# MirZ21_Sub-D.net
KiCad netlist of a schematic drawn in EAGLE
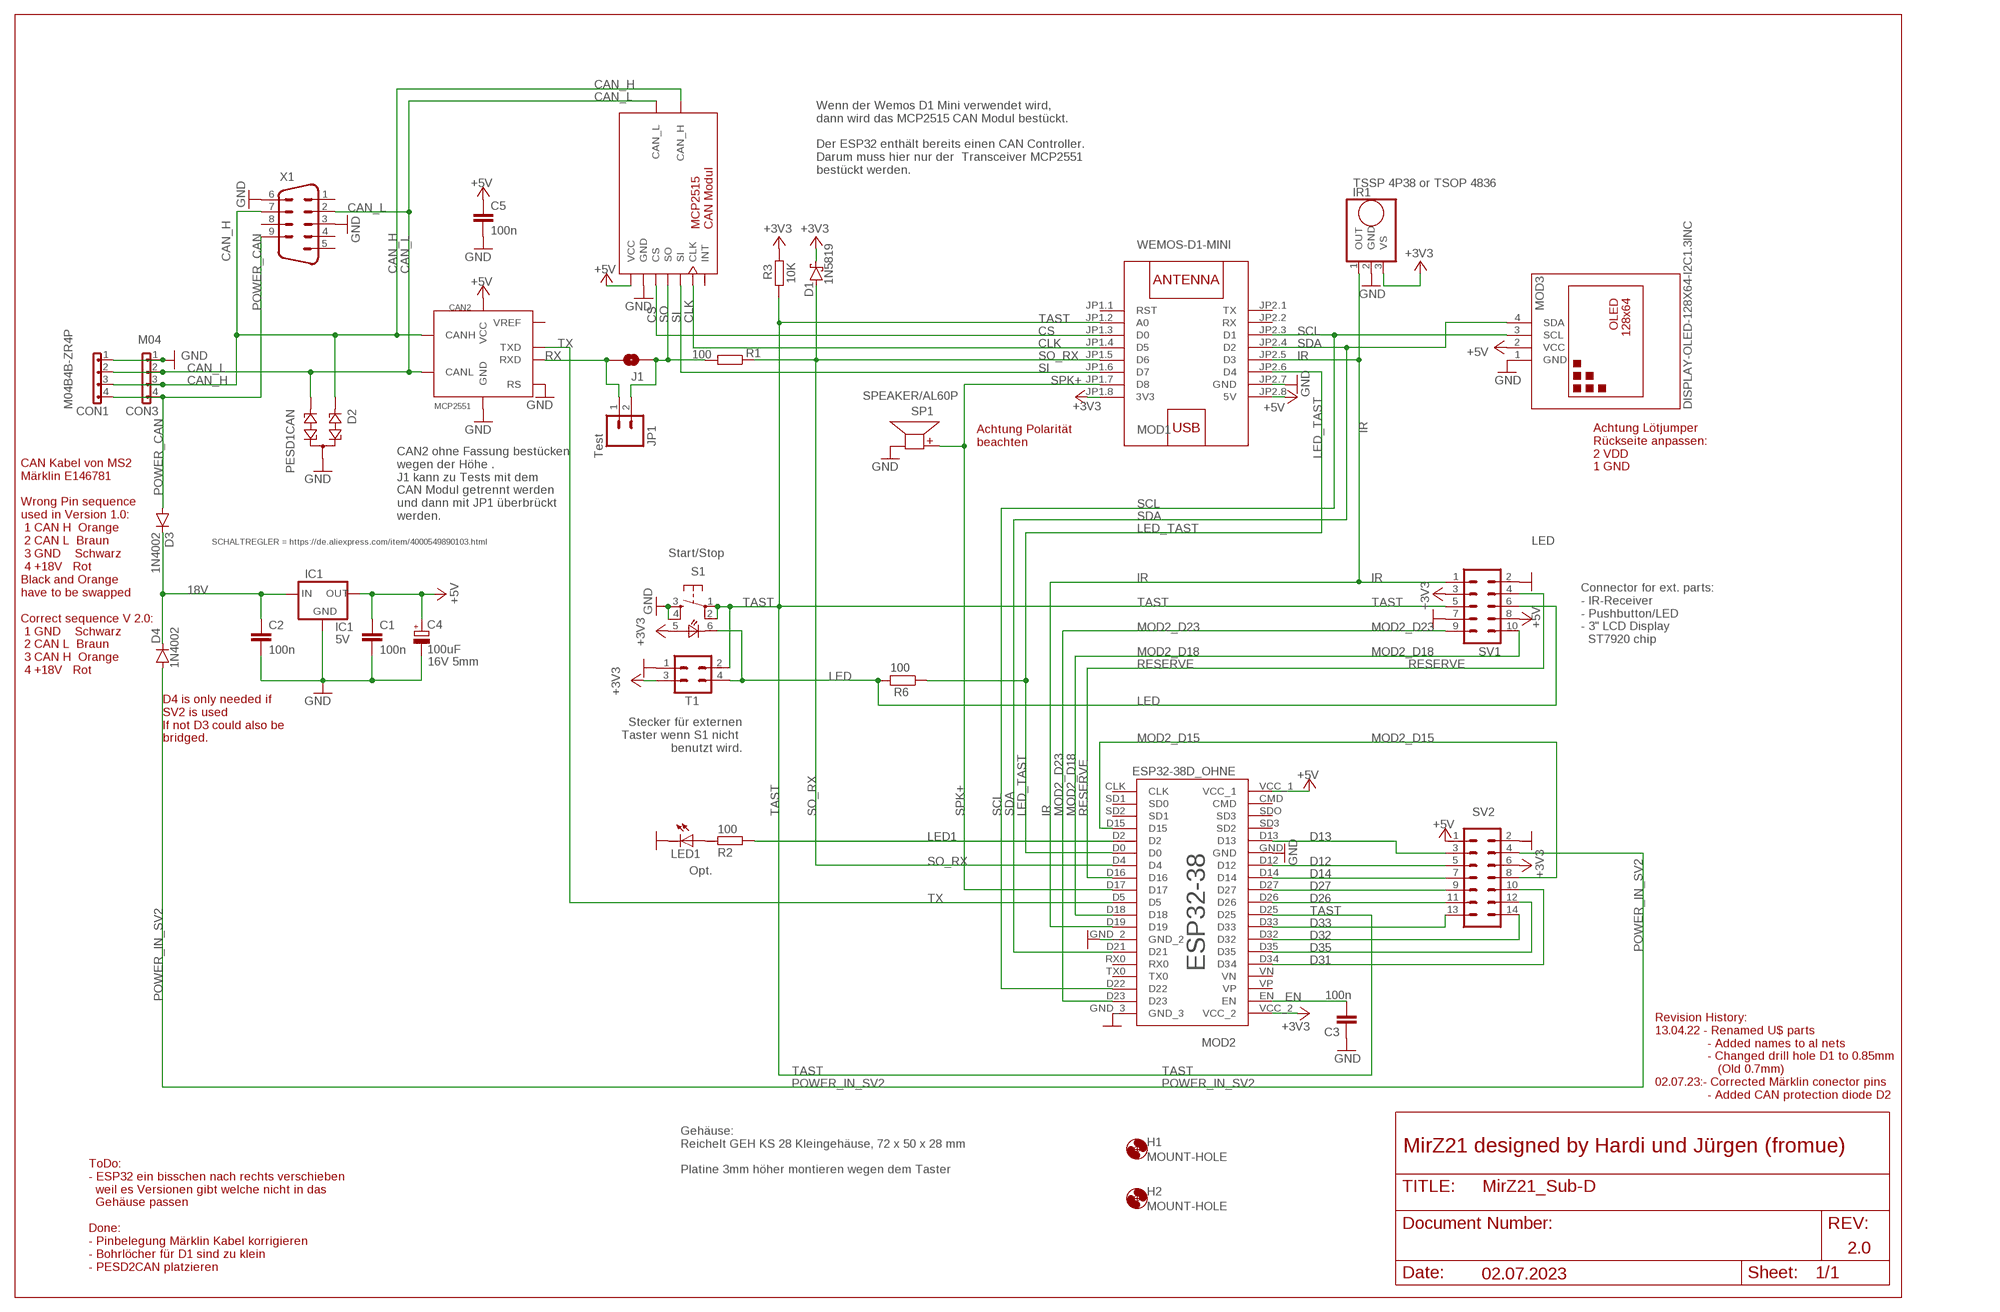
[diagram p0: schematic, sheet 1]

(export (version "E")
  (design (tool "Eeschema 10.0.6"))
  (components
    (comp (ref "C1")
      (value "100n")
      (footprint "eagle-import:C025-025X050")
      (libsource (lib "eagle-import") (part "C-EU025-025X050"))
    )
    (comp (ref "C2")
      (value "100n")
      (footprint "eagle-import:C025-025X050")
      (libsource (lib "eagle-import") (part "C-EU025-025X050"))
    )
    (comp (ref "C3")
      (value "100n")
      (footprint "eagle-import:C025-025X050")
      (libsource (lib "eagle-import") (part "C-EU025-025X050"))
    )
    (comp (ref "C4")
      (value "100uF")
      (footprint "eagle-import:TT2D5L")
      (fields (field (name "ADD") "16V 5mm"))
      (libsource (lib "eagle-import") (part "CPOL-EUTT2D5L"))
    )
    (comp (ref "C5")
      (value "100n")
      (footprint "eagle-import:C025-025X050")
      (libsource (lib "eagle-import") (part "C-EU025-025X050"))
    )
    (comp (ref "CAN1")
      (value "MCP2515_CAN_CUTCUT")
      (footprint "eagle-import:MCP2515_CAN_CUT")
      (libsource (lib "eagle-import") (part "MCP2515_CAN_CUTCUT"))
    )
    (comp (ref "CAN2")
      (value "MCP2551")
      (footprint "eagle-import:DIP08")
      (libsource (lib "eagle-import") (part "MCP2551DIP"))
    )
    (comp (ref "CON1")
      (value "M04B4B-ZR4P")
      (footprint "eagle-import:B4B-ZR4P")
      (libsource (lib "eagle-import") (part "M04B4B-ZR4P"))
    )
    (comp (ref "CON3")
      (value "M04")
      (footprint "eagle-import:1X04")
      (libsource (lib "eagle-import") (part "M04"))
    )
    (comp (ref "D1")
      (value "1N5819")
      (footprint "eagle-import:DO41-7.6")
      (libsource (lib "eagle-import") (part "1N581"))
    )
    (comp (ref "D2")
      (value "PESD1CAN")
      (footprint "eagle-import:SOT23")
      (libsource (lib "eagle-import") (part "PESD1CAN"))
    )
    (comp (ref "D3")
      (value "1N4002")
      (footprint "eagle-import:DO41-10")
      (libsource (lib "eagle-import") (part "1N4004"))
    )
    (comp (ref "D4")
      (value "1N4002")
      (footprint "eagle-import:DO41-10")
      (libsource (lib "eagle-import") (part "1N4004"))
    )
    (comp (ref "H1")
      (value "MOUNT-HOLE")
      (footprint "eagle-import:GEH_KS")
      (libsource (lib "eagle-import") (part "MOUNT-HOLE"))
    )
    (comp (ref "H2")
      (value "MOUNT-HOLE")
      (footprint "eagle-import:GEH_KS")
      (libsource (lib "eagle-import") (part "MOUNT-HOLE"))
    )
    (comp (ref "IC1")
      (value "5V")
      (footprint "eagle-import:HX1314G")
      (fields (field (name "SCHALTREGLER") "https://de.aliexpress.com/item/4000549890103.html"))
      (libsource (lib "eagle-import") (part "78XXSSTEPDOWN"))
    )
    (comp (ref "IR1")
      (value "TSSP 4P38 or TSOP 4836")
      (footprint "eagle-import:TSSP4P38")
      (libsource (lib "eagle-import") (part "TSSP4P38"))
    )
    (comp (ref "J1")
      (value "SOLDERJUMPERTRACE")
      (footprint "eagle-import:SJ_2S-TRACE")
      (libsource (lib "eagle-import") (part "SOLDERJUMPERTRACE"))
    )
    (comp (ref "JP1")
      (value "Test")
      (footprint "eagle-import:1X02")
      (libsource (lib "eagle-import") (part "M02PTH"))
    )
    (comp (ref "LED1")
      (value "Opt.")
      (footprint "eagle-import:LED3MM")
      (libsource (lib "eagle-import") (part "LED3MM"))
    )
    (comp (ref "MOD1")
      (value "WEMOS-D1-MINI")
      (footprint "eagle-import:WEMOS-D1-MINI")
      (libsource (lib "eagle-import") (part "WEMOS-D1-MINI"))
    )
    (comp (ref "MOD2")
      (value "ESP32-38D_OHNE")
      (footprint "eagle-import:ESP32-38D_0")
      (libsource (lib "eagle-import") (part "ESP32-38D_OHNE"))
    )
    (comp (ref "MOD3")
      (value "DISPLAY-OLED-128X64-I2C1.3INC")
      (footprint "eagle-import:DISPLAY-OLED-128X64-I2C-1.3")
      (libsource (lib "eagle-import") (part "DISPLAY-OLED-128X64-I2C1.3INC"))
    )
    (comp (ref "R1")
      (value "100")
      (footprint "eagle-import:0204_7")
      (libsource (lib "eagle-import") (part "R0204/7"))
    )
    (comp (ref "R2")
      (value "100")
      (footprint "eagle-import:0207_2V")
      (libsource (lib "eagle-import") (part "R-EU_0207/2V"))
    )
    (comp (ref "R3")
      (value "10K")
      (footprint "eagle-import:0204_7")
      (libsource (lib "eagle-import") (part "R0204/7"))
    )
    (comp (ref "R6")
      (value "100")
      (footprint "eagle-import:0204_7")
      (libsource (lib "eagle-import") (part "R0204/7"))
    )
    (comp (ref "S1")
      (value "TASTER_LEDTC-1198-B")
      (footprint "eagle-import:TASTER_LED")
      (libsource (lib "eagle-import") (part "TASTER_LEDTC-1198-B"))
    )
    (comp (ref "SP1")
      (value "SPEAKER/AL60P")
      (footprint "eagle-import:RMP-14SP")
      (libsource (lib "eagle-import") (part "SPEAKER/AL60P"))
    )
    (comp (ref "SV1")
      (value "ML10")
      (footprint "eagle-import:ML10")
      (libsource (lib "eagle-import") (part "ML10"))
    )
    (comp (ref "SV2")
      (value "ML14")
      (footprint "eagle-import:ML14")
      (libsource (lib "eagle-import") (part "ML14"))
    )
    (comp (ref "T1")
      (value "CON-HARTING-ML_ML4ML4_FEMALE")
      (footprint "eagle-import:ML_ML4_FEMALE")
      (libsource (lib "eagle-import") (part "CON-HARTING-ML_ML4ML4_FEMALE"))
    )
    (comp (ref "X1")
      (value "M09D")
      (footprint "eagle-import:M09D")
      (libsource (lib "eagle-import") (part "M09D"))
    )
  )
  (nets
    (net (code "1") (name "+3V3") (class "Default")
      (node (ref "D1") (pin "C") (pinfunction "C_C") (pintype "passive"))
      (node (ref "IR1") (pin "3") (pinfunction "VS_3") (pintype "power_in"))
      (node (ref "MOD1") (pin "JP1.8") (pinfunction "3V3_JP1.8") (pintype "power_in"))
      (node (ref "MOD2") (pin "VCC_2") (pinfunction "VCC_2_VCC_2") (pintype "power_in"))
      (node (ref "R3") (pin "2") (pinfunction "2_2") (pintype "passive"))
      (node (ref "S1") (pin "5") (pinfunction "+_5") (pintype "input"))
      (node (ref "SV1") (pin "3") (pinfunction "3_3") (pintype "passive"))
      (node (ref "SV2") (pin "6") (pinfunction "6_6") (pintype "passive"))
      (node (ref "T1") (pin "3") (pinfunction "3_3") (pintype "passive"))
    )
    (net (code "2") (name "+5V") (class "Default")
      (node (ref "C1") (pin "1") (pinfunction "1_1") (pintype "passive"))
      (node (ref "C4") (pin "+") (pinfunction "+_+") (pintype "passive"))
      (node (ref "C5") (pin "1") (pinfunction "1_1") (pintype "passive"))
      (node (ref "CAN1") (pin "1") (pinfunction "VCC_1") (pintype "power_in"))
      (node (ref "CAN2") (pin "3") (pinfunction "VCC_3") (pintype "power_in"))
      (node (ref "IC1") (pin "OUT") (pinfunction "OUT_OUT") (pintype "passive"))
      (node (ref "MOD1") (pin "JP2.8") (pinfunction "5V_JP2.8") (pintype "power_in"))
      (node (ref "MOD2") (pin "VCC_1") (pinfunction "VCC_1_VCC_1") (pintype "power_in"))
      (node (ref "MOD3") (pin "2") (pinfunction "VCC_2") (pintype "power_in"))
      (node (ref "SV1") (pin "8") (pinfunction "8_8") (pintype "passive"))
      (node (ref "SV2") (pin "1") (pinfunction "1_1") (pintype "passive"))
    )
    (net (code "3") (name "/18V") (class "Default")
      (node (ref "C2") (pin "1") (pinfunction "1_1") (pintype "passive"))
      (node (ref "D3") (pin "C") (pinfunction "C_C") (pintype "passive"))
      (node (ref "D4") (pin "C") (pinfunction "C_C") (pintype "passive"))
      (node (ref "IC1") (pin "IN") (pinfunction "IN_IN") (pintype "input"))
    )
    (net (code "4") (name "/CAN_H") (class "Default")
      (node (ref "CAN1") (pin "9") (pinfunction "CAN_H_9") (pintype "bidirectional"))
      (node (ref "CAN2") (pin "7") (pinfunction "CANH_7") (pintype "bidirectional"))
      (node (ref "CON1") (pin "3") (pinfunction "3_3") (pintype "passive"))
      (node (ref "CON3") (pin "3") (pinfunction "3_3") (pintype "passive"))
      (node (ref "D2") (pin "1") (pinfunction "1_1") (pintype "passive"))
      (node (ref "X1") (pin "7") (pinfunction "7_7") (pintype "passive"))
    )
    (net (code "5") (name "/CAN_L") (class "Default")
      (node (ref "CAN1") (pin "8") (pinfunction "CAN_L_8") (pintype "bidirectional"))
      (node (ref "CAN2") (pin "6") (pinfunction "CANL_6") (pintype "bidirectional"))
      (node (ref "CON1") (pin "2") (pinfunction "2_2") (pintype "passive"))
      (node (ref "CON3") (pin "2") (pinfunction "2_2") (pintype "passive"))
      (node (ref "D2") (pin "2") (pinfunction "2_2") (pintype "passive"))
      (node (ref "X1") (pin "2") (pinfunction "2_2") (pintype "passive"))
    )
    (net (code "6") (name "/CLK") (class "Default")
      (node (ref "CAN1") (pin "6") (pinfunction "CLK_6") (pintype "input"))
      (node (ref "MOD1") (pin "JP1.4") (pinfunction "D5_JP1.4") (pintype "bidirectional"))
    )
    (net (code "7") (name "/CS") (class "Default")
      (node (ref "CAN1") (pin "3") (pinfunction "CS_3") (pintype "input"))
      (node (ref "MOD1") (pin "JP1.3") (pinfunction "D0_JP1.3") (pintype "bidirectional"))
    )
    (net (code "8") (name "/D12") (class "Default")
      (node (ref "MOD2") (pin "D12") (pinfunction "D12_D12") (pintype "bidirectional"))
      (node (ref "SV2") (pin "5") (pinfunction "5_5") (pintype "passive"))
    )
    (net (code "9") (name "/D13") (class "Default")
      (node (ref "MOD2") (pin "D13") (pinfunction "D13_D13") (pintype "bidirectional"))
      (node (ref "SV2") (pin "3") (pinfunction "3_3") (pintype "passive"))
    )
    (net (code "10") (name "/D14") (class "Default")
      (node (ref "MOD2") (pin "D14") (pinfunction "D14_D14") (pintype "bidirectional"))
      (node (ref "SV2") (pin "7") (pinfunction "7_7") (pintype "passive"))
    )
    (net (code "11") (name "/D26") (class "Default")
      (node (ref "MOD2") (pin "D26") (pinfunction "D26_D26") (pintype "bidirectional"))
      (node (ref "SV2") (pin "11") (pinfunction "11_11") (pintype "passive"))
    )
    (net (code "12") (name "/D27") (class "Default")
      (node (ref "MOD2") (pin "D27") (pinfunction "D27_D27") (pintype "bidirectional"))
      (node (ref "SV2") (pin "9") (pinfunction "9_9") (pintype "passive"))
    )
    (net (code "13") (name "/D31") (class "Default")
      (node (ref "MOD2") (pin "D34") (pinfunction "D34_D34") (pintype "bidirectional"))
      (node (ref "SV2") (pin "10") (pinfunction "10_10") (pintype "passive"))
    )
    (net (code "14") (name "/D32") (class "Default")
      (node (ref "MOD2") (pin "D32") (pinfunction "D32_D32") (pintype "bidirectional"))
      (node (ref "SV2") (pin "14") (pinfunction "14_14") (pintype "passive"))
    )
    (net (code "15") (name "/D33") (class "Default")
      (node (ref "MOD2") (pin "D33") (pinfunction "D33_D33") (pintype "bidirectional"))
      (node (ref "SV2") (pin "13") (pinfunction "13_13") (pintype "passive"))
    )
    (net (code "16") (name "/D35") (class "Default")
      (node (ref "MOD2") (pin "D35") (pinfunction "D35_D35") (pintype "bidirectional"))
      (node (ref "SV2") (pin "12") (pinfunction "12_12") (pintype "passive"))
    )
    (net (code "17") (name "/EN") (class "Default")
      (node (ref "C3") (pin "2") (pinfunction "2_2") (pintype "passive"))
      (node (ref "MOD2") (pin "EN") (pinfunction "EN_EN") (pintype "input"))
    )
    (net (code "18") (name "/IR") (class "Default")
      (node (ref "IR1") (pin "1") (pinfunction "OUT_1") (pintype "output"))
      (node (ref "MOD1") (pin "JP2.5") (pinfunction "D3_JP2.5") (pintype "bidirectional"))
      (node (ref "MOD2") (pin "D19") (pinfunction "D19_D19") (pintype "bidirectional"))
      (node (ref "SV1") (pin "1") (pinfunction "1_1") (pintype "passive"))
    )
    (net (code "19") (name "/LED") (class "Default")
      (node (ref "R6") (pin "2") (pinfunction "2_2") (pintype "passive"))
      (node (ref "S1") (pin "6") (pinfunction "-_6") (pintype "input"))
      (node (ref "SV1") (pin "6") (pinfunction "6_6") (pintype "passive"))
      (node (ref "T1") (pin "4") (pinfunction "4_4") (pintype "passive"))
    )
    (net (code "20") (name "/LED1") (class "Default")
      (node (ref "MOD2") (pin "D2") (pinfunction "D2_D2") (pintype "bidirectional"))
      (node (ref "R2") (pin "2") (pinfunction "2_2") (pintype "passive"))
    )
    (net (code "21") (name "/LED_TAST") (class "Default")
      (node (ref "MOD1") (pin "JP2.6") (pinfunction "D4_JP2.6") (pintype "bidirectional"))
      (node (ref "MOD2") (pin "D0") (pinfunction "D0_D0") (pintype "input"))
      (node (ref "R6") (pin "1") (pinfunction "1_1") (pintype "passive"))
    )
    (net (code "22") (name "/MOD2_D15") (class "Default")
      (node (ref "MOD2") (pin "D15") (pinfunction "D15_D15") (pintype "bidirectional"))
      (node (ref "SV2") (pin "8") (pinfunction "8_8") (pintype "passive"))
    )
    (net (code "23") (name "/MOD2_D18") (class "Default")
      (node (ref "MOD2") (pin "D18") (pinfunction "D18_D18") (pintype "bidirectional"))
      (node (ref "SV1") (pin "10") (pinfunction "10_10") (pintype "passive"))
    )
    (net (code "24") (name "/MOD2_D23") (class "Default")
      (node (ref "MOD2") (pin "D23") (pinfunction "D23_D23") (pintype "bidirectional"))
      (node (ref "SV1") (pin "9") (pinfunction "9_9") (pintype "passive"))
    )
    (net (code "25") (name "/POWER_CAN") (class "Default")
      (node (ref "CON1") (pin "4") (pinfunction "4_4") (pintype "passive"))
      (node (ref "CON3") (pin "4") (pinfunction "4_4") (pintype "passive"))
      (node (ref "D3") (pin "A") (pinfunction "A_A") (pintype "passive"))
      (node (ref "X1") (pin "9") (pinfunction "9_9") (pintype "passive"))
    )
    (net (code "26") (name "/POWER_IN_SV2") (class "Default")
      (node (ref "D4") (pin "A") (pinfunction "A_A") (pintype "passive"))
      (node (ref "SV2") (pin "4") (pinfunction "4_4") (pintype "passive"))
    )
    (net (code "27") (name "/RESERVE") (class "Default")
      (node (ref "MOD2") (pin "D16") (pinfunction "D16_D16") (pintype "bidirectional"))
      (node (ref "SV1") (pin "4") (pinfunction "4_4") (pintype "passive"))
    )
    (net (code "28") (name "/RX") (class "Default")
      (node (ref "CAN2") (pin "4") (pinfunction "RXD_4") (pintype "power_in"))
      (node (ref "J1") (pin "2") (pinfunction "2_2") (pintype "passive"))
      (node (ref "JP1") (pin "1") (pinfunction "1_1") (pintype "passive"))
    )
    (net (code "29") (name "/SCL") (class "Default")
      (node (ref "MOD1") (pin "JP2.3") (pinfunction "D1_JP2.3") (pintype "bidirectional"))
      (node (ref "MOD2") (pin "D22") (pinfunction "D22_D22") (pintype "bidirectional"))
      (node (ref "MOD3") (pin "3") (pinfunction "SCL_3") (pintype "bidirectional"))
    )
    (net (code "30") (name "/SDA") (class "Default")
      (node (ref "MOD1") (pin "JP2.4") (pinfunction "D2_JP2.4") (pintype "bidirectional"))
      (node (ref "MOD2") (pin "D21") (pinfunction "D21_D21") (pintype "bidirectional"))
      (node (ref "MOD3") (pin "4") (pinfunction "SDA_4") (pintype "bidirectional"))
    )
    (net (code "31") (name "/SI") (class "Default")
      (node (ref "CAN1") (pin "5") (pinfunction "SI_5") (pintype "input"))
      (node (ref "MOD1") (pin "JP1.6") (pinfunction "D7_JP1.6") (pintype "bidirectional"))
    )
    (net (code "32") (name "/SO") (class "Default")
      (node (ref "CAN1") (pin "4") (pinfunction "SO_4") (pintype "output"))
      (node (ref "J1") (pin "1") (pinfunction "1_1") (pintype "passive"))
      (node (ref "JP1") (pin "2") (pinfunction "2_2") (pintype "passive"))
      (node (ref "R1") (pin "2") (pinfunction "2_2") (pintype "passive"))
    )
    (net (code "33") (name "/SO_RX") (class "Default")
      (node (ref "D1") (pin "A") (pinfunction "A_A") (pintype "passive"))
      (node (ref "MOD1") (pin "JP1.5") (pinfunction "D6_JP1.5") (pintype "bidirectional"))
      (node (ref "MOD2") (pin "D4") (pinfunction "D4_D4") (pintype "bidirectional"))
      (node (ref "R1") (pin "1") (pinfunction "1_1") (pintype "passive"))
    )
    (net (code "34") (name "/SPK+") (class "Default")
      (node (ref "MOD1") (pin "JP1.7") (pinfunction "D8_JP1.7") (pintype "bidirectional"))
      (node (ref "MOD2") (pin "D17") (pinfunction "D17_D17") (pintype "bidirectional"))
      (node (ref "SP1") (pin "1") (pinfunction "+_1") (pintype "passive"))
    )
    (net (code "35") (name "/TAST") (class "Default")
      (node (ref "MOD1") (pin "JP1.2") (pinfunction "A0_JP1.2") (pintype "bidirectional"))
      (node (ref "MOD2") (pin "D25") (pinfunction "D25_D25") (pintype "bidirectional"))
      (node (ref "R3") (pin "1") (pinfunction "1_1") (pintype "passive"))
      (node (ref "S1") (pin "1") (pinfunction "P_1") (pintype "passive"))
      (node (ref "S1") (pin "2") (pinfunction "P1_2") (pintype "passive"))
      (node (ref "SV1") (pin "5") (pinfunction "5_5") (pintype "passive"))
      (node (ref "T1") (pin "2") (pinfunction "2_2") (pintype "passive"))
    )
    (net (code "36") (name "/TX") (class "Default")
      (node (ref "CAN2") (pin "1") (pinfunction "TXD_1") (pintype "power_in"))
      (node (ref "MOD2") (pin "D5") (pinfunction "D5_D5") (pintype "bidirectional"))
    )
    (net (code "37") (name "/VREF") (class "Default")
      (node (ref "CAN2") (pin "5") (pinfunction "VREF_5") (pintype "power_in"))
    )
    (net (code "38") (name "GND") (class "Default")
      (node (ref "C1") (pin "2") (pinfunction "2_2") (pintype "passive"))
      (node (ref "C2") (pin "2") (pinfunction "2_2") (pintype "passive"))
      (node (ref "C3") (pin "1") (pinfunction "1_1") (pintype "passive"))
      (node (ref "C4") (pin "-") (pinfunction "-_-") (pintype "passive"))
      (node (ref "C5") (pin "2") (pinfunction "2_2") (pintype "passive"))
      (node (ref "CAN1") (pin "2") (pinfunction "GND_2") (pintype "power_in"))
      (node (ref "CAN2") (pin "2") (pinfunction "GND_2") (pintype "power_in"))
      (node (ref "CAN2") (pin "8") (pinfunction "RS_8") (pintype "power_in"))
      (node (ref "CON1") (pin "1") (pinfunction "1_1") (pintype "passive"))
      (node (ref "CON3") (pin "1") (pinfunction "1_1") (pintype "passive"))
      (node (ref "D2") (pin "3") (pinfunction "3_3") (pintype "passive"))
      (node (ref "IC1") (pin "GND") (pinfunction "GND_GND") (pintype "input"))
      (node (ref "IR1") (pin "2") (pinfunction "GND_2") (pintype "power_in"))
      (node (ref "LED1") (pin "K") (pinfunction "C_K") (pintype "passive"))
      (node (ref "MOD1") (pin "JP2.7") (pinfunction "GND_JP2.7") (pintype "power_in"))
      (node (ref "MOD2") (pin "GND") (pinfunction "GND_GND") (pintype "power_in"))
      (node (ref "MOD2") (pin "GND_2") (pinfunction "GND_2_GND_2") (pintype "power_in"))
      (node (ref "MOD2") (pin "GND_3") (pinfunction "GND_3_GND_3") (pintype "power_in"))
      (node (ref "MOD3") (pin "1") (pinfunction "GND_1") (pintype "power_in"))
      (node (ref "S1") (pin "3") (pinfunction "S_3") (pintype "passive"))
      (node (ref "S1") (pin "4") (pinfunction "S1_4") (pintype "passive"))
      (node (ref "SP1") (pin "2") (pinfunction "-_2") (pintype "passive"))
      (node (ref "SV1") (pin "2") (pinfunction "2_2") (pintype "passive"))
      (node (ref "SV1") (pin "7") (pinfunction "7_7") (pintype "passive"))
      (node (ref "SV2") (pin "2") (pinfunction "2_2") (pintype "passive"))
      (node (ref "T1") (pin "1") (pinfunction "1_1") (pintype "passive"))
      (node (ref "X1") (pin "3") (pinfunction "3_3") (pintype "passive"))
      (node (ref "X1") (pin "6") (pinfunction "6_6") (pintype "passive"))
    )
    (net (code "39") (name "Net-(LED1-PadA)") (class "Default")
      (node (ref "LED1") (pin "A") (pinfunction "A_A") (pintype "passive"))
      (node (ref "R2") (pin "1") (pinfunction "1_1") (pintype "passive"))
    )
    (net (code "40") (name "unconnected-(CAN1-INT-Pad7)") (class "Default")
      (node (ref "CAN1") (pin "7") (pinfunction "INT_7") (pintype "open_collector"))
    )
    (net (code "41") (name "unconnected-(MOD1-RST-PadJP1.1)") (class "Default")
      (node (ref "MOD1") (pin "JP1.1") (pinfunction "RST_JP1.1") (pintype "bidirectional"))
    )
    (net (code "42") (name "unconnected-(MOD1-RX-PadJP2.2)") (class "Default")
      (node (ref "MOD1") (pin "JP2.2") (pinfunction "RX_JP2.2") (pintype "bidirectional"))
    )
    (net (code "43") (name "unconnected-(MOD1-TX-PadJP2.1)") (class "Default")
      (node (ref "MOD1") (pin "JP2.1") (pinfunction "TX_JP2.1") (pintype "bidirectional"))
    )
    (net (code "44") (name "unconnected-(MOD2-PadCLK)") (class "Default")
      (node (ref "MOD2") (pin "CLK") (pinfunction "CLK_CLK") (pintype "no_connect"))
    )
    (net (code "45") (name "unconnected-(MOD2-PadCMD)") (class "Default")
      (node (ref "MOD2") (pin "CMD") (pinfunction "CMD_CMD") (pintype "no_connect"))
    )
    (net (code "46") (name "unconnected-(MOD2-PadRX0)") (class "Default")
      (node (ref "MOD2") (pin "RX0") (pinfunction "RX0_RX0") (pintype "bidirectional"))
    )
    (net (code "47") (name "unconnected-(MOD2-PadTX0)") (class "Default")
      (node (ref "MOD2") (pin "TX0") (pinfunction "TX0_TX0") (pintype "bidirectional"))
    )
    (net (code "48") (name "unconnected-(MOD2-PadVN)") (class "Default")
      (node (ref "MOD2") (pin "VN") (pinfunction "VN_VN") (pintype "bidirectional"))
    )
    (net (code "49") (name "unconnected-(MOD2-PadVP)") (class "Default")
      (node (ref "MOD2") (pin "VP") (pinfunction "VP_VP") (pintype "bidirectional"))
    )
    (net (code "50") (name "unconnected-(MOD2-SD0-PadSD1)") (class "Default")
      (node (ref "MOD2") (pin "SD1") (pinfunction "SD0_SD1") (pintype "no_connect"))
    )
    (net (code "51") (name "unconnected-(MOD2-SD1-PadSD2)") (class "Default")
      (node (ref "MOD2") (pin "SD2") (pinfunction "SD1_SD2") (pintype "no_connect"))
    )
    (net (code "52") (name "unconnected-(MOD2-SD2-PadSD3)") (class "Default")
      (node (ref "MOD2") (pin "SD3") (pinfunction "SD2_SD3") (pintype "no_connect"))
    )
    (net (code "53") (name "unconnected-(MOD2-SD3-PadSDO)") (class "Default")
      (node (ref "MOD2") (pin "SDO") (pinfunction "SD3_SDO") (pintype "no_connect"))
    )
    (net (code "54") (name "unconnected-(X1-Pad1)") (class "Default")
      (node (ref "X1") (pin "1") (pinfunction "1_1") (pintype "passive"))
    )
    (net (code "55") (name "unconnected-(X1-Pad4)") (class "Default")
      (node (ref "X1") (pin "4") (pinfunction "4_4") (pintype "passive"))
    )
    (net (code "56") (name "unconnected-(X1-Pad5)") (class "Default")
      (node (ref "X1") (pin "5") (pinfunction "5_5") (pintype "passive"))
    )
    (net (code "57") (name "unconnected-(X1-Pad8)") (class "Default")
      (node (ref "X1") (pin "8") (pinfunction "8_8") (pintype "passive"))
    )
  )
)
